# tinyPipes.net
KiCad netlist of a schematic drawn in EAGLE
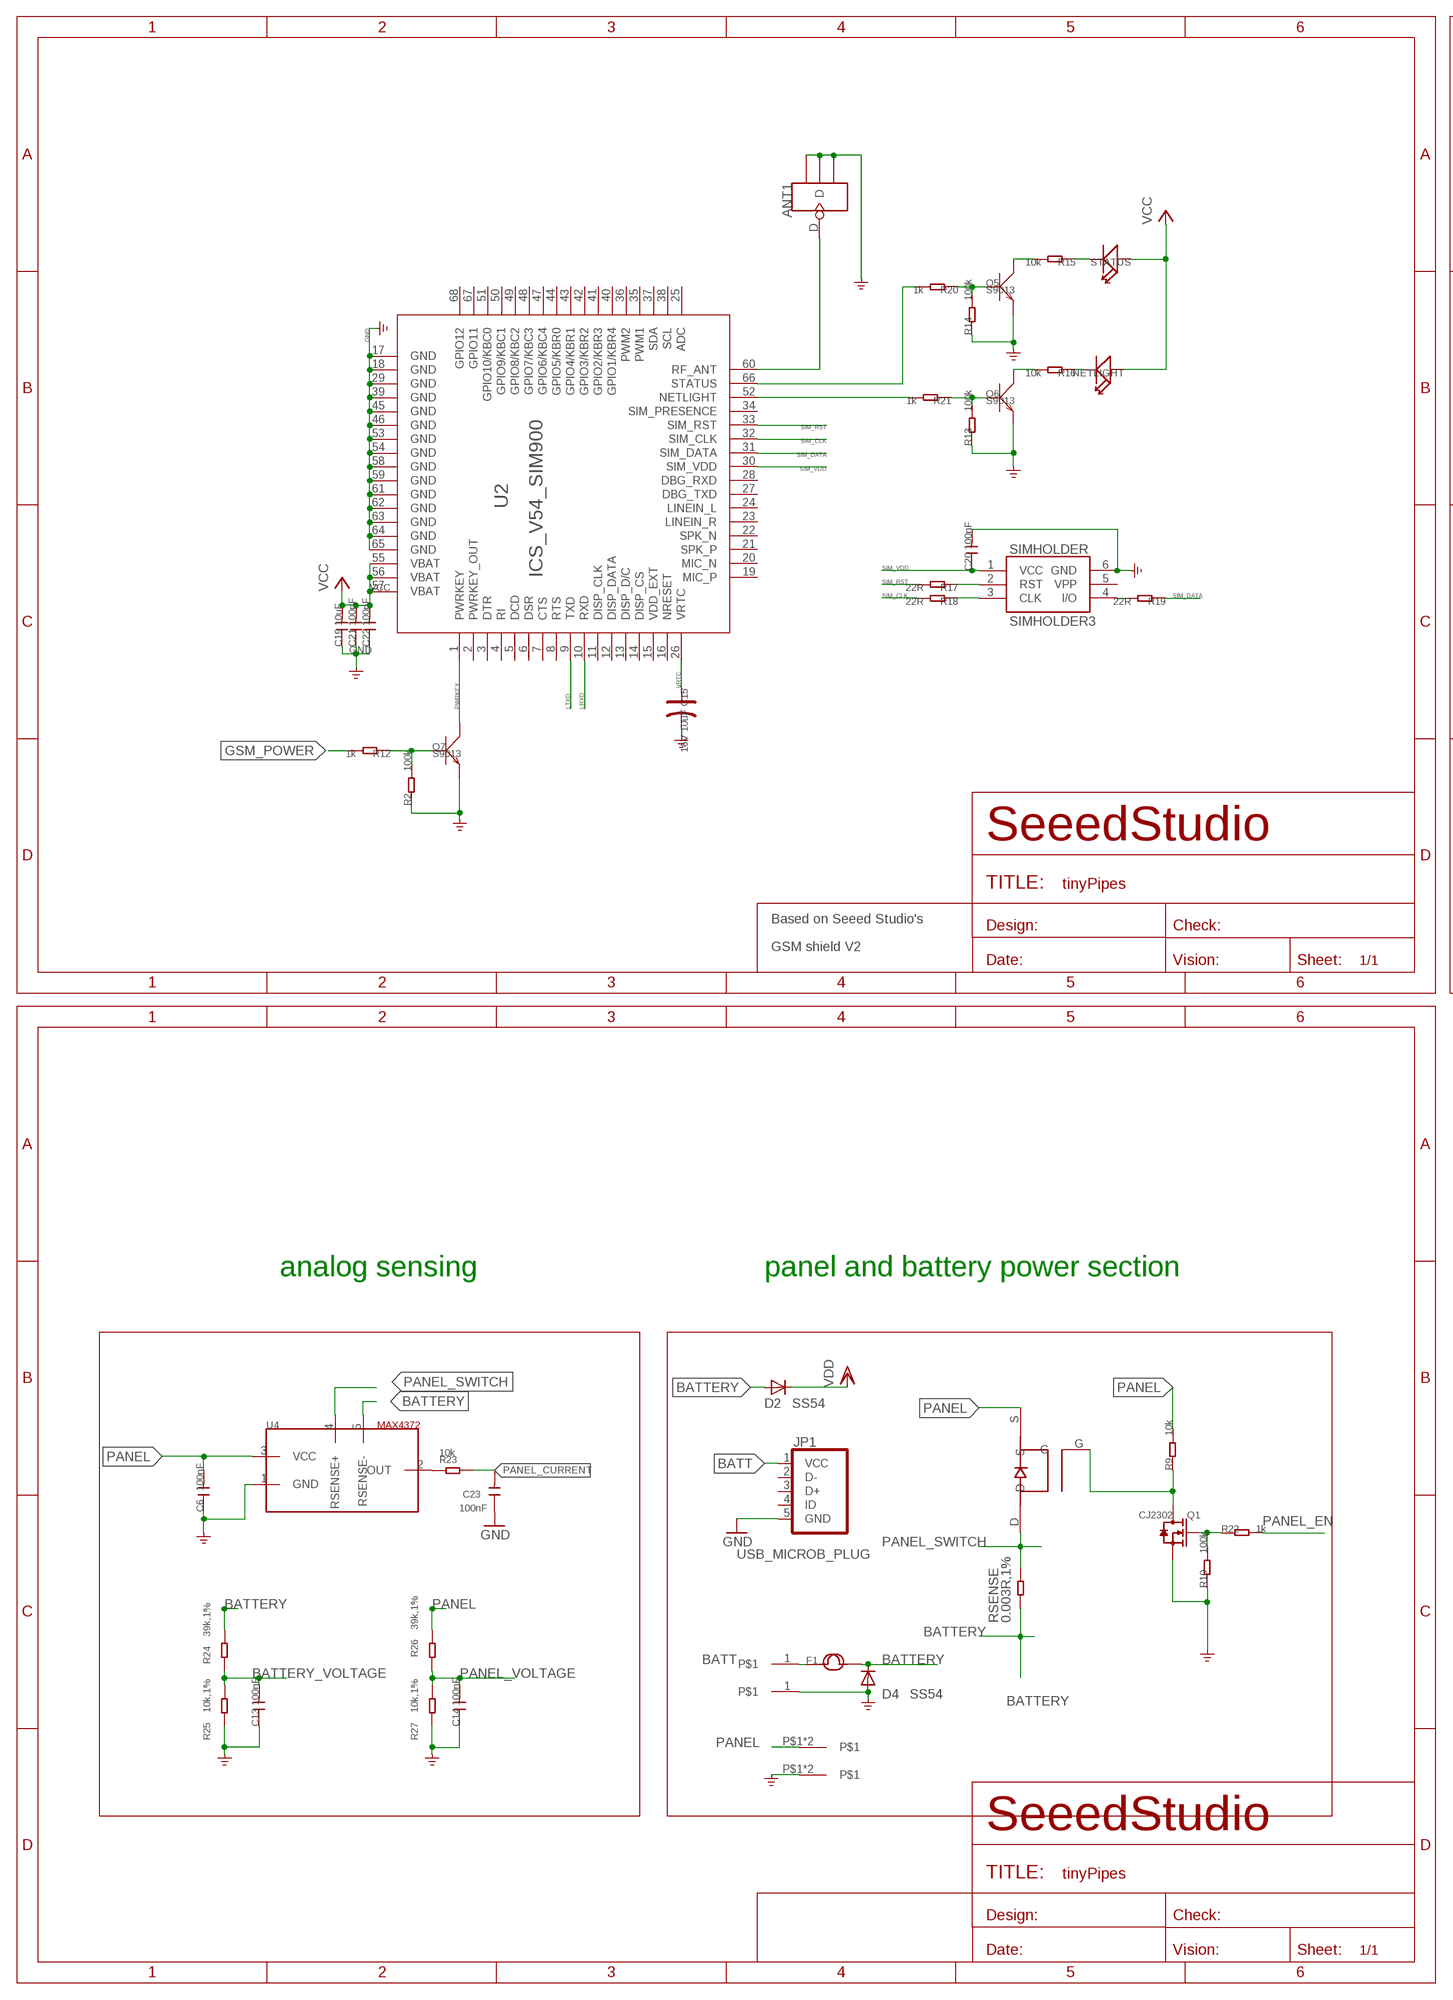
[diagram p0: schematic, sheet 1, part 1 of 2]
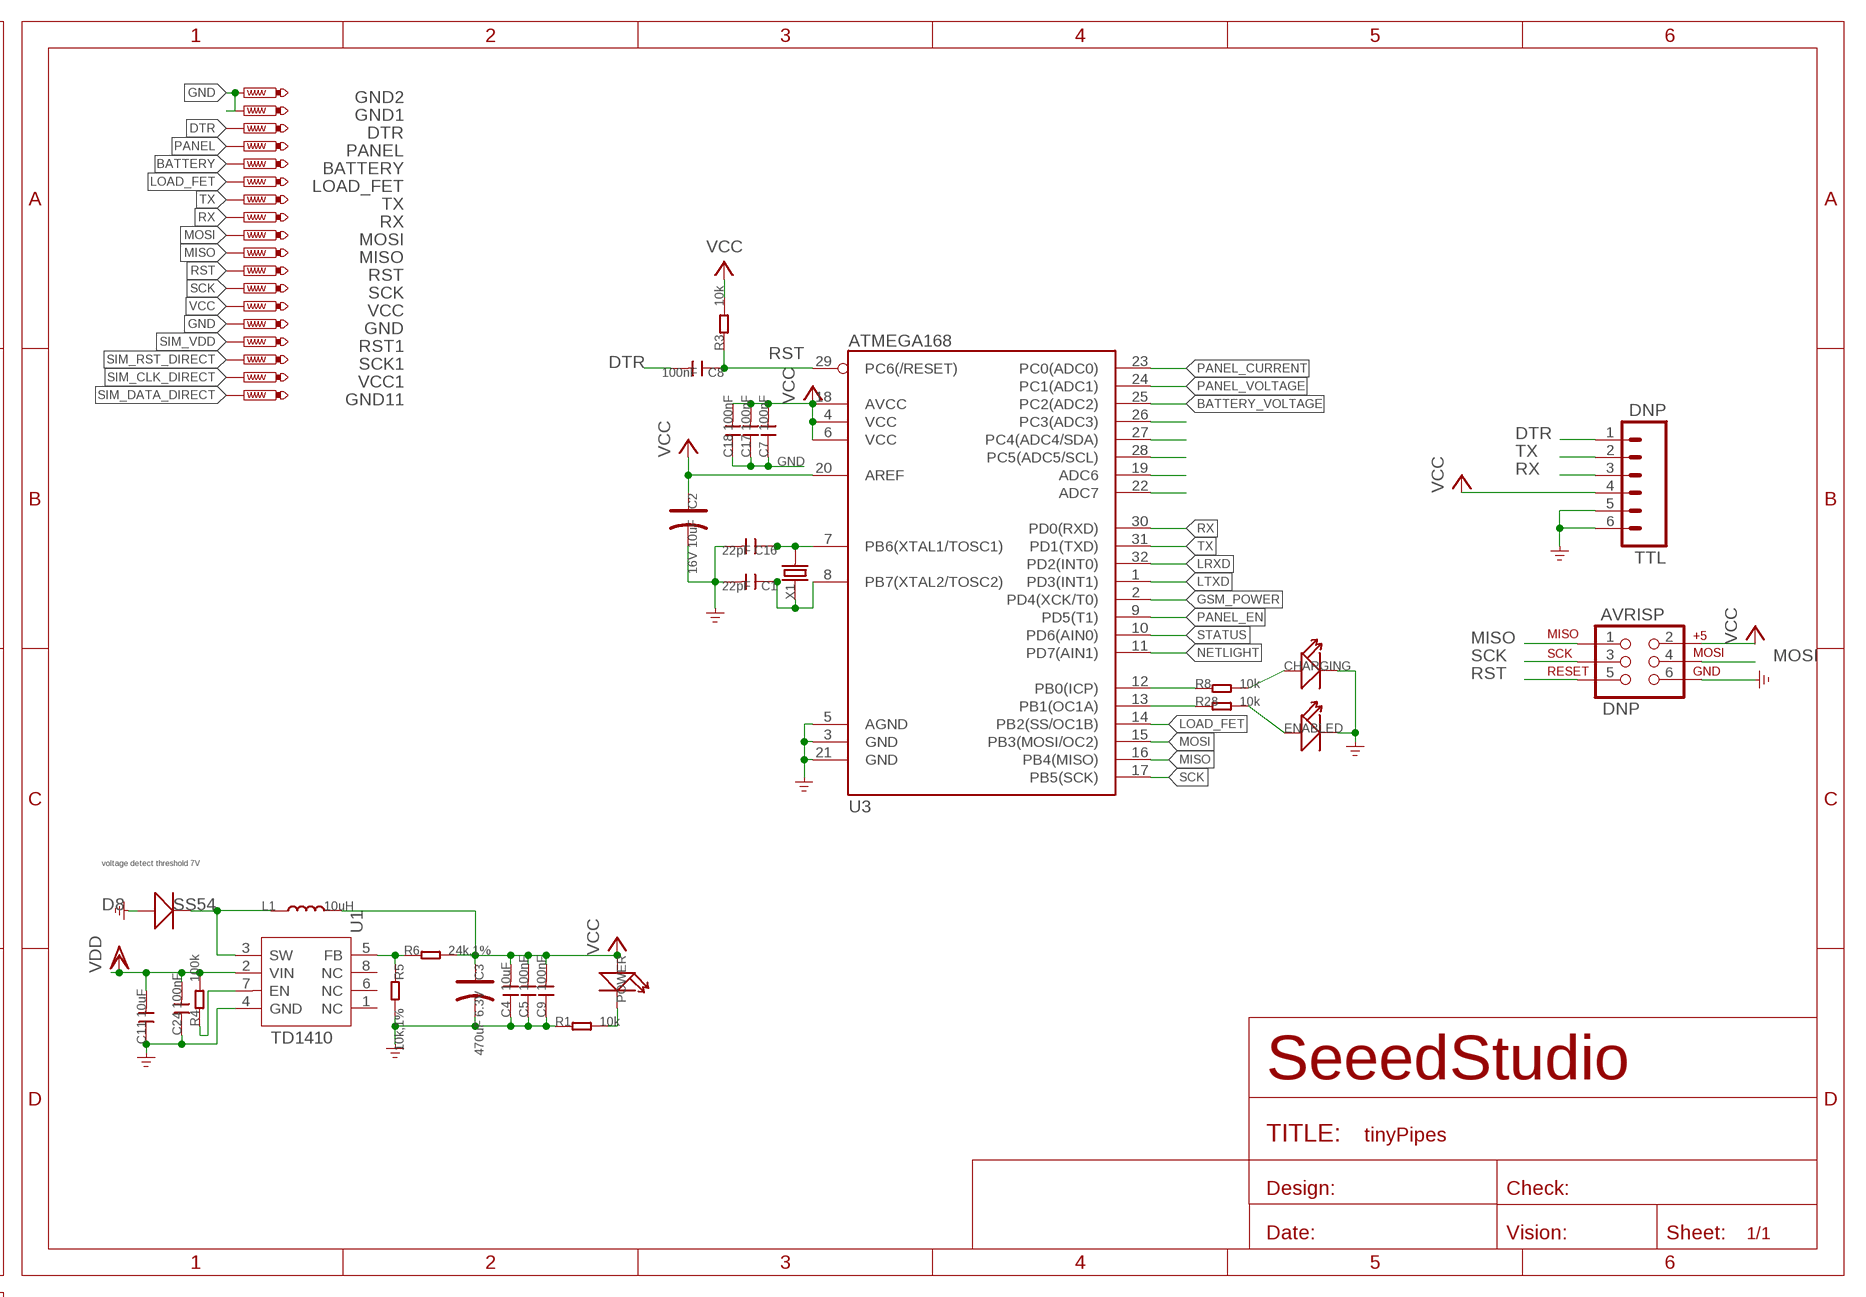
[diagram p1: schematic, sheet 1, part 2 of 2]

(export (version "E")
  (design (tool "Eeschema 10.0.6"))
  (components
    (comp (ref "ANT1")
      (value "ANTENNA-U-FL")
      (footprint "eagle-import:4P-U-FL")
      (libsource (lib "eagle-import") (part "ANTENNA-U-FL"))
    )
    (comp (ref "AVRISP")
      (value "DNP")
      (footprint "eagle-import:2X3_LOCK")
      (libsource (lib "eagle-import") (part "AVR_SPI_PRG_62X3_LOCK"))
    )
    (comp (ref "BATTERY")
      (value "HEARTPAD")
      (footprint "eagle-import:HEART")
      (libsource (lib "eagle-import") (part "HEARTPAD"))
    )
    (comp (ref "BATTERY+")
      (value "TINYPIPES_BATTBATT")
      (footprint "eagle-import:TINYPIPES_BATT")
      (libsource (lib "eagle-import") (part "TINYPIPES_BATTBATT"))
    )
    (comp (ref "BATTERY-")
      (value "TINYPIPES_BATTBATT")
      (footprint "eagle-import:TINYPIPES_BATT")
      (libsource (lib "eagle-import") (part "TINYPIPES_BATTBATT"))
    )
    (comp (ref "C1")
      (value "22pF")
      (footprint "eagle-import:C0603")
      (libsource (lib "eagle-import") (part "C-0603"))
    )
    (comp (ref "C2")
      (value "16V 10uF")
      (footprint "eagle-import:AVX-A")
      (libsource (lib "eagle-import") (part "CAP-AVX-A"))
    )
    (comp (ref "C3")
      (value "470uF 6.3V")
      (footprint "eagle-import:AVX-D")
      (libsource (lib "eagle-import") (part "CAP-AVX-D"))
    )
    (comp (ref "C4")
      (value "10uF")
      (footprint "eagle-import:C0805")
      (libsource (lib "eagle-import") (part "C-0805"))
    )
    (comp (ref "C5")
      (value "100nF")
      (footprint "eagle-import:C0603")
      (libsource (lib "eagle-import") (part "C-0603"))
    )
    (comp (ref "C6")
      (value "100nF")
      (footprint "eagle-import:C0603")
      (libsource (lib "eagle-import") (part "C-0603"))
    )
    (comp (ref "C7")
      (value "100nF")
      (footprint "eagle-import:C0603")
      (libsource (lib "eagle-import") (part "C-0603"))
    )
    (comp (ref "C8")
      (value "100nF")
      (footprint "eagle-import:C0603")
      (libsource (lib "eagle-import") (part "C-0603"))
    )
    (comp (ref "C9")
      (value "100nF")
      (footprint "eagle-import:C0603")
      (libsource (lib "eagle-import") (part "C-0603"))
    )
    (comp (ref "C11")
      (value "10uF")
      (footprint "eagle-import:C0805")
      (libsource (lib "eagle-import") (part "C-0805"))
    )
    (comp (ref "C13")
      (value "100nF")
      (footprint "eagle-import:C0603")
      (libsource (lib "eagle-import") (part "C-0603"))
    )
    (comp (ref "C14")
      (value "100nF")
      (footprint "eagle-import:C0603")
      (libsource (lib "eagle-import") (part "C-0603"))
    )
    (comp (ref "C15")
      (value "16V 10uF")
      (footprint "eagle-import:AVX-A")
      (libsource (lib "eagle-import") (part "CAP-AVX-A"))
    )
    (comp (ref "C16")
      (value "22pF")
      (footprint "eagle-import:C0603")
      (libsource (lib "eagle-import") (part "C-0603"))
    )
    (comp (ref "C17")
      (value "100nF")
      (footprint "eagle-import:C0603")
      (libsource (lib "eagle-import") (part "C-0603"))
    )
    (comp (ref "C18")
      (value "100nF")
      (footprint "eagle-import:C0603")
      (libsource (lib "eagle-import") (part "C-0603"))
    )
    (comp (ref "C19")
      (value "10uF")
      (footprint "eagle-import:C0805")
      (libsource (lib "eagle-import") (part "C-0805"))
    )
    (comp (ref "C20")
      (value "100nF")
      (footprint "eagle-import:C0603")
      (libsource (lib "eagle-import") (part "C-0603"))
    )
    (comp (ref "C21")
      (value "100nF")
      (footprint "eagle-import:C0603")
      (libsource (lib "eagle-import") (part "C-0603"))
    )
    (comp (ref "C22")
      (value "100nF")
      (footprint "eagle-import:C0603")
      (libsource (lib "eagle-import") (part "C-0603"))
    )
    (comp (ref "C23")
      (value "100nF")
      (footprint "eagle-import:C0805")
      (libsource (lib "eagle-import") (part "C-0805"))
    )
    (comp (ref "C24")
      (value "100nF")
      (footprint "eagle-import:C0603")
      (libsource (lib "eagle-import") (part "C-0603"))
    )
    (comp (ref "CHARGING")
      (value "LED'0603'")
      (footprint "eagle-import:LED-0603")
      (libsource (lib "eagle-import") (part "LED'0603'"))
    )
    (comp (ref "D2")
      (value "SS54")
      (footprint "eagle-import:SMB")
      (libsource (lib "eagle-import") (part "DIODE-SMB"))
    )
    (comp (ref "D4")
      (value "SS54")
      (footprint "eagle-import:SMB")
      (libsource (lib "eagle-import") (part "DIODE-SMB"))
    )
    (comp (ref "D8")
      (value "SS54")
      (footprint "eagle-import:SMB")
      (libsource (lib "eagle-import") (part "D'MBRS240LT3'"))
    )
    (comp (ref "DTR")
      (value "HEARTPAD")
      (footprint "eagle-import:HEART")
      (libsource (lib "eagle-import") (part "HEARTPAD"))
    )
    (comp (ref "ENABLED")
      (value "LED'0603'")
      (footprint "eagle-import:LED-0603")
      (libsource (lib "eagle-import") (part "LED'0603'"))
    )
    (comp (ref "F1")
      (value "FUSE'16R700'")
      (footprint "eagle-import:0210")
      (libsource (lib "eagle-import") (part "FUSE'16R700'"))
    )
    (comp (ref "GND")
      (value "HEARTPAD")
      (footprint "eagle-import:HEART")
      (libsource (lib "eagle-import") (part "HEARTPAD"))
    )
    (comp (ref "GND1")
      (value "HEARTPAD")
      (footprint "eagle-import:HEART")
      (libsource (lib "eagle-import") (part "HEARTPAD"))
    )
    (comp (ref "GND2")
      (value "HEARTPAD")
      (footprint "eagle-import:HEART")
      (libsource (lib "eagle-import") (part "HEARTPAD"))
    )
    (comp (ref "GND11")
      (value "HEARTPAD")
      (footprint "eagle-import:HEART")
      (libsource (lib "eagle-import") (part "HEARTPAD"))
    )
    (comp (ref "JP1")
      (value "USB_MICROB_PLUG")
      (footprint "eagle-import:MICRO-B-RA-SMT")
      (libsource (lib "eagle-import") (part "USB_MICROB_PLUG"))
    )
    (comp (ref "L1")
      (value "10uH")
      (footprint "eagle-import:L0630")
      (libsource (lib "eagle-import") (part "L'0630'"))
    )
    (comp (ref "LOAD_FET")
      (value "HEARTPAD")
      (footprint "eagle-import:HEART")
      (libsource (lib "eagle-import") (part "HEARTPAD"))
    )
    (comp (ref "MISO")
      (value "HEARTPAD")
      (footprint "eagle-import:HEART")
      (libsource (lib "eagle-import") (part "HEARTPAD"))
    )
    (comp (ref "MOSI")
      (value "HEARTPAD")
      (footprint "eagle-import:HEART")
      (libsource (lib "eagle-import") (part "HEARTPAD"))
    )
    (comp (ref "NETLIGHT")
      (value "LED'0603'")
      (footprint "eagle-import:LED-0603")
      (libsource (lib "eagle-import") (part "LED'0603'"))
    )
    (comp (ref "PANEL")
      (value "HEARTPAD")
      (footprint "eagle-import:HEART")
      (libsource (lib "eagle-import") (part "HEARTPAD"))
    )
    (comp (ref "PANEL+")
      (value "TINYPIPES_BATTPANEL")
      (footprint "eagle-import:TINYPIPES_PANEL")
      (libsource (lib "eagle-import") (part "TINYPIPES_BATTPANEL"))
    )
    (comp (ref "PANEL-")
      (value "TINYPIPES_BATTPANEL")
      (footprint "eagle-import:TINYPIPES_PANEL")
      (libsource (lib "eagle-import") (part "TINYPIPES_BATTPANEL"))
    )
    (comp (ref "POWER")
      (value "LED'0603'")
      (footprint "eagle-import:LED-0603")
      (libsource (lib "eagle-import") (part "LED'0603'"))
    )
    (comp (ref "Q1")
      (value "CJ2302")
      (footprint "eagle-import:SOT23")
      (libsource (lib "eagle-import") (part "MOSFET-N'SOT23'"))
    )
    (comp (ref "Q5")
      (value "S9013")
      (footprint "eagle-import:SOT23")
      (libsource (lib "eagle-import") (part "TRANSISTOR-NPN-SOT23"))
    )
    (comp (ref "Q6")
      (value "S9013")
      (footprint "eagle-import:SOT23")
      (libsource (lib "eagle-import") (part "TRANSISTOR-NPN-SOT23"))
    )
    (comp (ref "Q7")
      (value "S9013")
      (footprint "eagle-import:SOT23")
      (libsource (lib "eagle-import") (part "TRANSISTOR-NPN-SOT23"))
    )
    (comp (ref "R1")
      (value "10k")
      (footprint "eagle-import:R0603")
      (libsource (lib "eagle-import") (part "R-0603"))
    )
    (comp (ref "R2")
      (value "100k")
      (footprint "eagle-import:R0603")
      (libsource (lib "eagle-import") (part "R-0603"))
    )
    (comp (ref "R3")
      (value "10k")
      (footprint "eagle-import:R0603")
      (libsource (lib "eagle-import") (part "R-0603"))
    )
    (comp (ref "R4")
      (value "100k")
      (footprint "eagle-import:R0603")
      (libsource (lib "eagle-import") (part "R-0603"))
    )
    (comp (ref "R5")
      (value "10k,1%")
      (footprint "eagle-import:R0603")
      (libsource (lib "eagle-import") (part "R-0603"))
    )
    (comp (ref "R6")
      (value "24k,1%")
      (footprint "eagle-import:R0603")
      (libsource (lib "eagle-import") (part "R-0603"))
    )
    (comp (ref "R8")
      (value "10k")
      (footprint "eagle-import:R0603")
      (libsource (lib "eagle-import") (part "R-0603"))
    )
    (comp (ref "R9")
      (value "10k")
      (footprint "eagle-import:R0603")
      (libsource (lib "eagle-import") (part "R-0603"))
    )
    (comp (ref "R10")
      (value "100k")
      (footprint "eagle-import:R0603")
      (libsource (lib "eagle-import") (part "R-0603"))
    )
    (comp (ref "R12")
      (value "1k")
      (footprint "eagle-import:R0603")
      (libsource (lib "eagle-import") (part "R-0603"))
    )
    (comp (ref "R13")
      (value "100k")
      (footprint "eagle-import:R0603")
      (libsource (lib "eagle-import") (part "R-0603"))
    )
    (comp (ref "R14")
      (value "100k")
      (footprint "eagle-import:R0603")
      (libsource (lib "eagle-import") (part "R-0603"))
    )
    (comp (ref "R15")
      (value "10k")
      (footprint "eagle-import:R0603")
      (libsource (lib "eagle-import") (part "R-0603"))
    )
    (comp (ref "R16")
      (value "10k")
      (footprint "eagle-import:R0603")
      (libsource (lib "eagle-import") (part "R-0603"))
    )
    (comp (ref "R17")
      (value "22R")
      (footprint "eagle-import:R0603")
      (libsource (lib "eagle-import") (part "R-0603"))
    )
    (comp (ref "R18")
      (value "22R")
      (footprint "eagle-import:R0603")
      (libsource (lib "eagle-import") (part "R-0603"))
    )
    (comp (ref "R19")
      (value "22R")
      (footprint "eagle-import:R0603")
      (libsource (lib "eagle-import") (part "R-0603"))
    )
    (comp (ref "R20")
      (value "1k")
      (footprint "eagle-import:R0603")
      (libsource (lib "eagle-import") (part "R-0603"))
    )
    (comp (ref "R21")
      (value "1k")
      (footprint "eagle-import:R0603")
      (libsource (lib "eagle-import") (part "R-0603"))
    )
    (comp (ref "R22")
      (value "1k")
      (footprint "eagle-import:R0603")
      (libsource (lib "eagle-import") (part "R-0603"))
    )
    (comp (ref "R23")
      (value "10k")
      (footprint "eagle-import:R0603")
      (libsource (lib "eagle-import") (part "R-0603"))
    )
    (comp (ref "R24")
      (value "39k,1%")
      (footprint "eagle-import:R0603")
      (libsource (lib "eagle-import") (part "R-0603"))
    )
    (comp (ref "R25")
      (value "10k,1%")
      (footprint "eagle-import:R0603")
      (libsource (lib "eagle-import") (part "R-0603"))
    )
    (comp (ref "R26")
      (value "39k,1%")
      (footprint "eagle-import:R0603")
      (libsource (lib "eagle-import") (part "R-0603"))
    )
    (comp (ref "R27")
      (value "10k,1%")
      (footprint "eagle-import:R0603")
      (libsource (lib "eagle-import") (part "R-0603"))
    )
    (comp (ref "R28")
      (value "10k")
      (footprint "eagle-import:R0603")
      (libsource (lib "eagle-import") (part "R-0603"))
    )
    (comp (ref "RSENSE")
      (value "0.003R,1%")
      (footprint "eagle-import:R2512")
      (libsource (lib "eagle-import") (part "R-2512"))
    )
    (comp (ref "RST")
      (value "HEARTPAD")
      (footprint "eagle-import:HEART")
      (libsource (lib "eagle-import") (part "HEARTPAD"))
    )
    (comp (ref "RST1")
      (value "HEARTPAD")
      (footprint "eagle-import:HEART")
      (libsource (lib "eagle-import") (part "HEARTPAD"))
    )
    (comp (ref "RX")
      (value "HEARTPAD")
      (footprint "eagle-import:HEART")
      (libsource (lib "eagle-import") (part "HEARTPAD"))
    )
    (comp (ref "SCK")
      (value "HEARTPAD")
      (footprint "eagle-import:HEART")
      (libsource (lib "eagle-import") (part "HEARTPAD"))
    )
    (comp (ref "SCK1")
      (value "HEARTPAD")
      (footprint "eagle-import:HEART")
      (libsource (lib "eagle-import") (part "HEARTPAD"))
    )
    (comp (ref "SIMHOLDER")
      (value "SIMHOLDER3")
      (footprint "eagle-import:SIMHOLDER3")
      (libsource (lib "eagle-import") (part "SIMHOLDER3"))
    )
    (comp (ref "STATUS")
      (value "LED'0603'")
      (footprint "eagle-import:LED-0603")
      (libsource (lib "eagle-import") (part "LED'0603'"))
    )
    (comp (ref "TTL")
      (value "DNP")
      (footprint "eagle-import:1X06_LOCK")
      (libsource (lib "eagle-import") (part "M06LOCK"))
    )
    (comp (ref "TX")
      (value "HEARTPAD")
      (footprint "eagle-import:HEART")
      (libsource (lib "eagle-import") (part "HEARTPAD"))
    )
    (comp (ref "U1")
      (value "TD1410")
      (footprint "eagle-import:SOP8")
      (libsource (lib "eagle-import") (part "TD1410"))
    )
    (comp (ref "U2")
      (value "ICS_V54_SIM900")
      (footprint "eagle-import:ICS_V54_SIM900")
      (libsource (lib "eagle-import") (part "ICS_V54_SIM900"))
    )
    (comp (ref "U3")
      (value "ATMEGA168")
      (footprint "eagle-import:TQFP32-08")
      (libsource (lib "eagle-import") (part "ATMEGA168"))
    )
    (comp (ref "U4")
      (value "MAX4372")
      (footprint "eagle-import:SOT23-5")
      (libsource (lib "eagle-import") (part "MAX4372"))
    )
    (comp (ref "U5")
      (value "SI4435POWER")
      (footprint "eagle-import:SO8_FET")
      (libsource (lib "eagle-import") (part "SI4435POWER"))
    )
    (comp (ref "VCC")
      (value "HEARTPAD")
      (footprint "eagle-import:HEART")
      (libsource (lib "eagle-import") (part "HEARTPAD"))
    )
    (comp (ref "VCC1")
      (value "HEARTPAD")
      (footprint "eagle-import:HEART")
      (libsource (lib "eagle-import") (part "HEARTPAD"))
    )
    (comp (ref "X1")
      (value "CRYSTAL'5032'")
      (footprint "eagle-import:2P-SMD-5X3.2")
      (libsource (lib "eagle-import") (part "CRYSTAL'5032'"))
    )
  )
  (nets
    (net (code "1") (name "/PWRKEY") (class "Default")
      (node (ref "Q7") (pin "3") (pinfunction "C_3") (pintype "passive"))
      (node (ref "U2") (pin "1") (pinfunction "PWRKEY_1") (pintype "input"))
    )
    (net (code "2") (name "/SIM_CLK") (class "Default")
      (node (ref "R18") (pin "2") (pinfunction "2_2") (pintype "passive"))
      (node (ref "U2") (pin "32") (pinfunction "SIM_CLK_32") (pintype "output"))
    )
    (net (code "3") (name "/SIM_DATA") (class "Default")
      (node (ref "R19") (pin "1") (pinfunction "1_1") (pintype "passive"))
      (node (ref "U2") (pin "31") (pinfunction "SIM_DATA_31") (pintype "bidirectional"))
    )
    (net (code "4") (name "/SIM_RST") (class "Default")
      (node (ref "R17") (pin "2") (pinfunction "2_2") (pintype "passive"))
      (node (ref "U2") (pin "33") (pinfunction "SIM_RST_33") (pintype "output"))
    )
    (net (code "5") (name "/VRTC") (class "Default")
      (node (ref "C15") (pin "+") (pinfunction "+_+") (pintype "passive"))
      (node (ref "U2") (pin "26") (pinfunction "VRTC_26") (pintype "bidirectional"))
    )
    (net (code "6") (name "BATT") (class "Default")
      (node (ref "BATTERY+") (pin "1") (pinfunction "P$1_1") (pintype "bidirectional"))
      (node (ref "F1") (pin "1") (pinfunction "1_1") (pintype "bidirectional"))
      (node (ref "JP1") (pin "1") (pinfunction "VCC_1") (pintype "bidirectional"))
    )
    (net (code "7") (name "BATTERY") (class "Default")
      (node (ref "BATTERY") (pin "P$1") (pinfunction "TP_P$1") (pintype "input"))
      (node (ref "D2") (pin "A") (pinfunction "A_A") (pintype "passive"))
      (node (ref "D4") (pin "C") (pinfunction "C_C") (pintype "passive"))
      (node (ref "F1") (pin "2") (pinfunction "2_2") (pintype "bidirectional"))
      (node (ref "R24") (pin "2") (pinfunction "2_2") (pintype "passive"))
      (node (ref "RSENSE") (pin "1") (pinfunction "1_1") (pintype "passive"))
      (node (ref "U4") (pin "5") (pinfunction "RSENSE-_5") (pintype "bidirectional"))
    )
    (net (code "8") (name "BATTERY_VOLTAGE") (class "Default")
      (node (ref "C13") (pin "2") (pinfunction "2_2") (pintype "passive"))
      (node (ref "R24") (pin "1") (pinfunction "1_1") (pintype "passive"))
      (node (ref "R25") (pin "2") (pinfunction "2_2") (pintype "passive"))
      (node (ref "U3") (pin "25") (pinfunction "PC2(ADC2)_25") (pintype "bidirectional"))
    )
    (net (code "9") (name "DTR") (class "Default")
      (node (ref "C8") (pin "2") (pinfunction "2_2") (pintype "passive"))
      (node (ref "DTR") (pin "P$1") (pinfunction "TP_P$1") (pintype "input"))
      (node (ref "TTL") (pin "1") (pinfunction "1_1") (pintype "passive"))
    )
    (net (code "10") (name "GND") (class "Default")
      (node (ref "ANT1") (pin "GND1") (pinfunction "GND1_GND1") (pintype "bidirectional"))
      (node (ref "ANT1") (pin "GND2") (pinfunction "GND2_GND2") (pintype "bidirectional"))
      (node (ref "ANT1") (pin "GND3") (pinfunction "GND3_GND3") (pintype "bidirectional"))
      (node (ref "AVRISP") (pin "6") (pinfunction "6_6") (pintype "passive"))
      (node (ref "BATTERY-") (pin "1") (pinfunction "P$1_1") (pintype "bidirectional"))
      (node (ref "C1") (pin "2") (pinfunction "2_2") (pintype "passive"))
      (node (ref "C11") (pin "1") (pinfunction "1_1") (pintype "passive"))
      (node (ref "C13") (pin "1") (pinfunction "1_1") (pintype "passive"))
      (node (ref "C14") (pin "1") (pinfunction "1_1") (pintype "passive"))
      (node (ref "C15") (pin "-") (pinfunction "-_-") (pintype "passive"))
      (node (ref "C16") (pin "2") (pinfunction "2_2") (pintype "passive"))
      (node (ref "C17") (pin "1") (pinfunction "1_1") (pintype "passive"))
      (node (ref "C18") (pin "1") (pinfunction "1_1") (pintype "passive"))
      (node (ref "C19") (pin "1") (pinfunction "1_1") (pintype "passive"))
      (node (ref "C2") (pin "-") (pinfunction "-_-") (pintype "passive"))
      (node (ref "C20") (pin "2") (pinfunction "2_2") (pintype "passive"))
      (node (ref "C21") (pin "1") (pinfunction "1_1") (pintype "passive"))
      (node (ref "C22") (pin "1") (pinfunction "1_1") (pintype "passive"))
      (node (ref "C23") (pin "1") (pinfunction "1_1") (pintype "passive"))
      (node (ref "C24") (pin "1") (pinfunction "1_1") (pintype "passive"))
      (node (ref "C3") (pin "-") (pinfunction "-_-") (pintype "passive"))
      (node (ref "C4") (pin "1") (pinfunction "1_1") (pintype "passive"))
      (node (ref "C5") (pin "1") (pinfunction "1_1") (pintype "passive"))
      (node (ref "C6") (pin "1") (pinfunction "1_1") (pintype "passive"))
      (node (ref "C7") (pin "1") (pinfunction "1_1") (pintype "passive"))
      (node (ref "C9") (pin "1") (pinfunction "1_1") (pintype "passive"))
      (node (ref "CHARGING") (pin "-") (pinfunction "-_-") (pintype "passive"))
      (node (ref "D4") (pin "A") (pinfunction "A_A") (pintype "passive"))
      (node (ref "D8") (pin "+") (pinfunction "+_+") (pintype "passive"))
      (node (ref "ENABLED") (pin "-") (pinfunction "-_-") (pintype "passive"))
      (node (ref "GND") (pin "P$1") (pinfunction "TP_P$1") (pintype "input"))
      (node (ref "GND1") (pin "P$1") (pinfunction "TP_P$1") (pintype "input"))
      (node (ref "GND2") (pin "P$1") (pinfunction "TP_P$1") (pintype "input"))
      (node (ref "JP1") (pin "5") (pinfunction "GND_5") (pintype "bidirectional"))
      (node (ref "PANEL-") (pin "P$1") (pinfunction "P$1_P$1") (pintype "bidirectional"))
      (node (ref "PANEL-") (pin "P$2") (pinfunction "P$1_P$2") (pintype "bidirectional"))
      (node (ref "Q1") (pin "2") (pinfunction "S_2") (pintype "passive"))
      (node (ref "Q5") (pin "2") (pinfunction "E_2") (pintype "passive"))
      (node (ref "Q6") (pin "2") (pinfunction "E_2") (pintype "passive"))
      (node (ref "Q7") (pin "2") (pinfunction "E_2") (pintype "passive"))
      (node (ref "R1") (pin "1") (pinfunction "1_1") (pintype "passive"))
      (node (ref "R10") (pin "1") (pinfunction "1_1") (pintype "passive"))
      (node (ref "R13") (pin "1") (pinfunction "1_1") (pintype "passive"))
      (node (ref "R14") (pin "1") (pinfunction "1_1") (pintype "passive"))
      (node (ref "R2") (pin "1") (pinfunction "1_1") (pintype "passive"))
      (node (ref "R25") (pin "1") (pinfunction "1_1") (pintype "passive"))
      (node (ref "R27") (pin "1") (pinfunction "1_1") (pintype "passive"))
      (node (ref "R5") (pin "2") (pinfunction "2_2") (pintype "passive"))
      (node (ref "SIMHOLDER") (pin "6") (pinfunction "GND_6") (pintype "bidirectional"))
      (node (ref "TTL") (pin "5") (pinfunction "5_5") (pintype "passive"))
      (node (ref "TTL") (pin "6") (pinfunction "6_6") (pintype "passive"))
      (node (ref "U1") (pin "4") (pinfunction "GND_4") (pintype "power_in"))
      (node (ref "U2") (pin "17") (pinfunction "GND_17") (pintype "power_in"))
      (node (ref "U2") (pin "18") (pinfunction "GND_18") (pintype "power_in"))
      (node (ref "U2") (pin "29") (pinfunction "GND_29") (pintype "power_in"))
      (node (ref "U2") (pin "39") (pinfunction "GND_39") (pintype "power_in"))
      (node (ref "U2") (pin "45") (pinfunction "GND_45") (pintype "power_in"))
      (node (ref "U2") (pin "46") (pinfunction "GND_46") (pintype "power_in"))
      (node (ref "U2") (pin "53") (pinfunction "GND_53") (pintype "power_in"))
      (node (ref "U2") (pin "54") (pinfunction "GND_54") (pintype "power_in"))
      (node (ref "U2") (pin "58") (pinfunction "GND_58") (pintype "power_in"))
      (node (ref "U2") (pin "59") (pinfunction "GND_59") (pintype "power_in"))
      (node (ref "U2") (pin "61") (pinfunction "GND_61") (pintype "power_in"))
      (node (ref "U2") (pin "62") (pinfunction "GND_62") (pintype "power_in"))
      (node (ref "U2") (pin "63") (pinfunction "GND_63") (pintype "power_in"))
      (node (ref "U2") (pin "64") (pinfunction "GND_64") (pintype "power_in"))
      (node (ref "U2") (pin "65") (pinfunction "GND_65") (pintype "power_in"))
      (node (ref "U3") (pin "21") (pinfunction "GND_21") (pintype "bidirectional"))
      (node (ref "U3") (pin "3") (pinfunction "GND_3") (pintype "bidirectional"))
      (node (ref "U3") (pin "5") (pinfunction "AGND_5") (pintype "bidirectional"))
      (node (ref "U4") (pin "1") (pinfunction "GND_1") (pintype "bidirectional"))
    )
    (net (code "11") (name "GSM_POWER") (class "Default")
      (node (ref "R12") (pin "2") (pinfunction "2_2") (pintype "passive"))
      (node (ref "U3") (pin "2") (pinfunction "PD4(XCK/T0)_2") (pintype "bidirectional"))
    )
    (net (code "12") (name "LOAD_FET") (class "Default")
      (node (ref "LOAD_FET") (pin "P$1") (pinfunction "TP_P$1") (pintype "input"))
      (node (ref "U3") (pin "14") (pinfunction "PB2(SS/OC1B)_14") (pintype "bidirectional"))
    )
    (net (code "13") (name "LRXD") (class "Default")
      (node (ref "U2") (pin "10") (pinfunction "RXD_10") (pintype "input"))
      (node (ref "U3") (pin "32") (pinfunction "PD2(INT0)_32") (pintype "bidirectional"))
    )
    (net (code "14") (name "LTXD") (class "Default")
      (node (ref "U2") (pin "9") (pinfunction "TXD_9") (pintype "output"))
      (node (ref "U3") (pin "1") (pinfunction "PD3(INT1)_1") (pintype "bidirectional"))
    )
    (net (code "15") (name "MISO") (class "Default")
      (node (ref "AVRISP") (pin "1") (pinfunction "1_1") (pintype "passive"))
      (node (ref "MISO") (pin "P$1") (pinfunction "TP_P$1") (pintype "input"))
      (node (ref "U3") (pin "16") (pinfunction "PB4(MISO)_16") (pintype "bidirectional"))
    )
    (net (code "16") (name "MOSI") (class "Default")
      (node (ref "AVRISP") (pin "4") (pinfunction "4_4") (pintype "passive"))
      (node (ref "MOSI") (pin "P$1") (pinfunction "TP_P$1") (pintype "input"))
      (node (ref "U3") (pin "15") (pinfunction "PB3(MOSI/OC2)_15") (pintype "bidirectional"))
    )
    (net (code "17") (name "NETLIGHT") (class "Default")
      (node (ref "R21") (pin "2") (pinfunction "2_2") (pintype "passive"))
      (node (ref "U2") (pin "52") (pinfunction "NETLIGHT_52") (pintype "output"))
      (node (ref "U3") (pin "11") (pinfunction "PD7(AIN1)_11") (pintype "bidirectional"))
    )
    (net (code "18") (name "Net-(CHARGING-Pad+)") (class "Default")
      (node (ref "CHARGING") (pin "+") (pinfunction "+_+") (pintype "passive"))
      (node (ref "R8") (pin "2") (pinfunction "2_2") (pintype "passive"))
    )
    (net (code "19") (name "Net-(ENABLED-Pad+)") (class "Default")
      (node (ref "ENABLED") (pin "+") (pinfunction "+_+") (pintype "passive"))
      (node (ref "R28") (pin "2") (pinfunction "2_2") (pintype "passive"))
    )
    (net (code "20") (name "Net-(NETLIGHT-Pad-)") (class "Default")
      (node (ref "NETLIGHT") (pin "-") (pinfunction "-_-") (pintype "passive"))
      (node (ref "R16") (pin "1") (pinfunction "1_1") (pintype "passive"))
    )
    (net (code "21") (name "Net-(POWER-Pad-)") (class "Default")
      (node (ref "POWER") (pin "-") (pinfunction "-_-") (pintype "passive"))
      (node (ref "R1") (pin "2") (pinfunction "2_2") (pintype "passive"))
    )
    (net (code "22") (name "Net-(Q1-D)") (class "Default")
      (node (ref "Q1") (pin "3") (pinfunction "D_3") (pintype "passive"))
      (node (ref "R9") (pin "1") (pinfunction "1_1") (pintype "passive"))
      (node (ref "U5") (pin "G") (pinfunction "G_G") (pintype "bidirectional"))
    )
    (net (code "23") (name "Net-(Q1-G)") (class "Default")
      (node (ref "Q1") (pin "1") (pinfunction "G_1") (pintype "passive"))
      (node (ref "R10") (pin "2") (pinfunction "2_2") (pintype "passive"))
      (node (ref "R22") (pin "1") (pinfunction "1_1") (pintype "passive"))
    )
    (net (code "24") (name "Net-(Q5-B)") (class "Default")
      (node (ref "Q5") (pin "1") (pinfunction "B_1") (pintype "passive"))
      (node (ref "R14") (pin "2") (pinfunction "2_2") (pintype "passive"))
      (node (ref "R20") (pin "1") (pinfunction "1_1") (pintype "passive"))
    )
    (net (code "25") (name "Net-(Q5-C)") (class "Default")
      (node (ref "Q5") (pin "3") (pinfunction "C_3") (pintype "passive"))
      (node (ref "R15") (pin "2") (pinfunction "2_2") (pintype "passive"))
    )
    (net (code "26") (name "Net-(Q6-B)") (class "Default")
      (node (ref "Q6") (pin "1") (pinfunction "B_1") (pintype "passive"))
      (node (ref "R13") (pin "2") (pinfunction "2_2") (pintype "passive"))
      (node (ref "R21") (pin "1") (pinfunction "1_1") (pintype "passive"))
    )
    (net (code "27") (name "Net-(Q6-C)") (class "Default")
      (node (ref "Q6") (pin "3") (pinfunction "C_3") (pintype "passive"))
      (node (ref "R16") (pin "2") (pinfunction "2_2") (pintype "passive"))
    )
    (net (code "28") (name "Net-(Q7-B)") (class "Default")
      (node (ref "Q7") (pin "1") (pinfunction "B_1") (pintype "passive"))
      (node (ref "R12") (pin "1") (pinfunction "1_1") (pintype "passive"))
      (node (ref "R2") (pin "2") (pinfunction "2_2") (pintype "passive"))
    )
    (net (code "29") (name "Net-(R15-Pad1)") (class "Default")
      (node (ref "R15") (pin "1") (pinfunction "1_1") (pintype "passive"))
      (node (ref "STATUS") (pin "-") (pinfunction "-_-") (pintype "passive"))
    )
    (net (code "30") (name "Net-(U1-EN)") (class "Default")
      (node (ref "R4") (pin "1") (pinfunction "1_1") (pintype "passive"))
      (node (ref "U1") (pin "7") (pinfunction "EN_7") (pintype "input"))
    )
    (net (code "31") (name "Net-(U1-FB)") (class "Default")
      (node (ref "R5") (pin "1") (pinfunction "1_1") (pintype "passive"))
      (node (ref "R6") (pin "1") (pinfunction "1_1") (pintype "passive"))
      (node (ref "U1") (pin "5") (pinfunction "FB_5") (pintype "input"))
    )
    (net (code "32") (name "Net-(U1-SW)") (class "Default")
      (node (ref "D8") (pin "-") (pinfunction "-_-") (pintype "passive"))
      (node (ref "L1") (pin "1") (pinfunction "1_1") (pintype "passive"))
      (node (ref "U1") (pin "3") (pinfunction "SW_3") (pintype "output"))
    )
    (net (code "33") (name "Net-(U2-RF_ANT)") (class "Default")
      (node (ref "ANT1") (pin "D") (pinfunction "D_D") (pintype "bidirectional"))
      (node (ref "U2") (pin "60") (pinfunction "RF_ANT_60") (pintype "bidirectional"))
    )
    (net (code "34") (name "Net-(U3-PB0(ICP))") (class "Default")
      (node (ref "R8") (pin "1") (pinfunction "1_1") (pintype "passive"))
      (node (ref "U3") (pin "12") (pinfunction "PB0(ICP)_12") (pintype "bidirectional"))
    )
    (net (code "35") (name "Net-(U3-PB1(OC1A))") (class "Default")
      (node (ref "R28") (pin "1") (pinfunction "1_1") (pintype "passive"))
      (node (ref "U3") (pin "13") (pinfunction "PB1(OC1A)_13") (pintype "bidirectional"))
    )
    (net (code "36") (name "Net-(U3-PB6(XTAL1{slash}TOSC1))") (class "Default")
      (node (ref "C16") (pin "1") (pinfunction "1_1") (pintype "passive"))
      (node (ref "U3") (pin "7") (pinfunction "PB6(XTAL1/TOSC1)_7") (pintype "bidirectional"))
      (node (ref "X1") (pin "2") (pinfunction "2_2") (pintype "passive"))
    )
    (net (code "37") (name "Net-(U3-PB7(XTAL2{slash}TOSC2))") (class "Default")
      (node (ref "C1") (pin "1") (pinfunction "1_1") (pintype "passive"))
      (node (ref "U3") (pin "8") (pinfunction "PB7(XTAL2/TOSC2)_8") (pintype "bidirectional"))
      (node (ref "X1") (pin "1") (pinfunction "1_1") (pintype "passive"))
    )
    (net (code "38") (name "Net-(U4-OUT)") (class "Default")
      (node (ref "R23") (pin "1") (pinfunction "1_1") (pintype "passive"))
      (node (ref "U4") (pin "2") (pinfunction "OUT_2") (pintype "bidirectional"))
    )
    (net (code "39") (name "PANEL") (class "Default")
      (node (ref "C6") (pin "2") (pinfunction "2_2") (pintype "passive"))
      (node (ref "PANEL") (pin "P$1") (pinfunction "TP_P$1") (pintype "input"))
      (node (ref "PANEL+") (pin "P$1") (pinfunction "P$1_P$1") (pintype "bidirectional"))
      (node (ref "PANEL+") (pin "P$2") (pinfunction "P$1_P$2") (pintype "bidirectional"))
      (node (ref "R26") (pin "2") (pinfunction "2_2") (pintype "passive"))
      (node (ref "R9") (pin "2") (pinfunction "2_2") (pintype "passive"))
      (node (ref "U4") (pin "3") (pinfunction "VCC_3") (pintype "bidirectional"))
      (node (ref "U5") (pin "S") (pinfunction "S_S") (pintype "bidirectional"))
    )
    (net (code "40") (name "PANEL_CURRENT") (class "Default")
      (node (ref "C23") (pin "2") (pinfunction "2_2") (pintype "passive"))
      (node (ref "R23") (pin "2") (pinfunction "2_2") (pintype "passive"))
      (node (ref "U3") (pin "23") (pinfunction "PC0(ADC0)_23") (pintype "bidirectional"))
    )
    (net (code "41") (name "PANEL_EN") (class "Default")
      (node (ref "R22") (pin "2") (pinfunction "2_2") (pintype "passive"))
      (node (ref "U3") (pin "9") (pinfunction "PD5(T1)_9") (pintype "bidirectional"))
    )
    (net (code "42") (name "PANEL_SWITCH") (class "Default")
      (node (ref "RSENSE") (pin "2") (pinfunction "2_2") (pintype "passive"))
      (node (ref "U4") (pin "4") (pinfunction "RSENSE+_4") (pintype "bidirectional"))
      (node (ref "U5") (pin "D") (pinfunction "D_D") (pintype "bidirectional"))
    )
    (net (code "43") (name "PANEL_VOLTAGE") (class "Default")
      (node (ref "C14") (pin "2") (pinfunction "2_2") (pintype "passive"))
      (node (ref "R26") (pin "1") (pinfunction "1_1") (pintype "passive"))
      (node (ref "R27") (pin "2") (pinfunction "2_2") (pintype "passive"))
      (node (ref "U3") (pin "24") (pinfunction "PC1(ADC1)_24") (pintype "bidirectional"))
    )
    (net (code "44") (name "RST") (class "Default")
      (node (ref "AVRISP") (pin "5") (pinfunction "5_5") (pintype "passive"))
      (node (ref "C8") (pin "1") (pinfunction "1_1") (pintype "passive"))
      (node (ref "R3") (pin "1") (pinfunction "1_1") (pintype "passive"))
      (node (ref "RST") (pin "P$1") (pinfunction "TP_P$1") (pintype "input"))
      (node (ref "U3") (pin "29") (pinfunction "PC6(/RESET)_29") (pintype "bidirectional"))
    )
    (net (code "45") (name "RX") (class "Default")
      (node (ref "RX") (pin "P$1") (pinfunction "TP_P$1") (pintype "input"))
      (node (ref "TTL") (pin "3") (pinfunction "3_3") (pintype "passive"))
      (node (ref "U3") (pin "30") (pinfunction "PD0(RXD)_30") (pintype "bidirectional"))
    )
    (net (code "46") (name "SCK") (class "Default")
      (node (ref "AVRISP") (pin "3") (pinfunction "3_3") (pintype "passive"))
      (node (ref "SCK") (pin "P$1") (pinfunction "TP_P$1") (pintype "input"))
      (node (ref "U3") (pin "17") (pinfunction "PB5(SCK)_17") (pintype "bidirectional"))
    )
    (net (code "47") (name "SIM_CLK_DIRECT") (class "Default")
      (node (ref "R18") (pin "1") (pinfunction "1_1") (pintype "passive"))
      (node (ref "SIMHOLDER") (pin "3") (pinfunction "CLK_3") (pintype "bidirectional"))
      (node (ref "VCC1") (pin "P$1") (pinfunction "TP_P$1") (pintype "input"))
    )
    (net (code "48") (name "SIM_DATA_DIRECT") (class "Default")
      (node (ref "GND11") (pin "P$1") (pinfunction "TP_P$1") (pintype "input"))
      (node (ref "R19") (pin "2") (pinfunction "2_2") (pintype "passive"))
      (node (ref "SIMHOLDER") (pin "4") (pinfunction "I/O_4") (pintype "bidirectional"))
    )
    (net (code "49") (name "SIM_RST_DIRECT") (class "Default")
      (node (ref "R17") (pin "1") (pinfunction "1_1") (pintype "passive"))
      (node (ref "SCK1") (pin "P$1") (pinfunction "TP_P$1") (pintype "input"))
      (node (ref "SIMHOLDER") (pin "2") (pinfunction "RST_2") (pintype "bidirectional"))
    )
    (net (code "50") (name "SIM_VDD") (class "Default")
      (node (ref "C20") (pin "1") (pinfunction "1_1") (pintype "passive"))
      (node (ref "RST1") (pin "P$1") (pinfunction "TP_P$1") (pintype "input"))
      (node (ref "SIMHOLDER") (pin "1") (pinfunction "VCC_1") (pintype "bidirectional"))
      (node (ref "U2") (pin "30") (pinfunction "SIM_VDD_30") (pintype "output"))
    )
    (net (code "51") (name "STATUS") (class "Default")
      (node (ref "R20") (pin "2") (pinfunction "2_2") (pintype "passive"))
      (node (ref "U2") (pin "66") (pinfunction "STATUS_66") (pintype "output"))
      (node (ref "U3") (pin "10") (pinfunction "PD6(AIN0)_10") (pintype "bidirectional"))
    )
    (net (code "52") (name "TX") (class "Default")
      (node (ref "TTL") (pin "2") (pinfunction "2_2") (pintype "passive"))
      (node (ref "TX") (pin "P$1") (pinfunction "TP_P$1") (pintype "input"))
      (node (ref "U3") (pin "31") (pinfunction "PD1(TXD)_31") (pintype "bidirectional"))
    )
    (net (code "53") (name "VCC") (class "Default")
      (node (ref "AVRISP") (pin "2") (pinfunction "2_2") (pintype "passive"))
      (node (ref "C17") (pin "2") (pinfunction "2_2") (pintype "passive"))
      (node (ref "C18") (pin "2") (pinfunction "2_2") (pintype "passive"))
      (node (ref "C19") (pin "2") (pinfunction "2_2") (pintype "passive"))
      (node (ref "C2") (pin "+") (pinfunction "+_+") (pintype "passive"))
      (node (ref "C21") (pin "2") (pinfunction "2_2") (pintype "passive"))
      (node (ref "C22") (pin "2") (pinfunction "2_2") (pintype "passive"))
      (node (ref "C3") (pin "+") (pinfunction "+_+") (pintype "passive"))
      (node (ref "C4") (pin "2") (pinfunction "2_2") (pintype "passive"))
      (node (ref "C5") (pin "2") (pinfunction "2_2") (pintype "passive"))
      (node (ref "C7") (pin "2") (pinfunction "2_2") (pintype "passive"))
      (node (ref "C9") (pin "2") (pinfunction "2_2") (pintype "passive"))
      (node (ref "L1") (pin "2") (pinfunction "2_2") (pintype "passive"))
      (node (ref "NETLIGHT") (pin "+") (pinfunction "+_+") (pintype "passive"))
      (node (ref "POWER") (pin "+") (pinfunction "+_+") (pintype "passive"))
      (node (ref "R3") (pin "2") (pinfunction "2_2") (pintype "passive"))
      (node (ref "R6") (pin "2") (pinfunction "2_2") (pintype "passive"))
      (node (ref "STATUS") (pin "+") (pinfunction "+_+") (pintype "passive"))
      (node (ref "TTL") (pin "4") (pinfunction "4_4") (pintype "passive"))
      (node (ref "U2") (pin "55") (pinfunction "VBAT_55") (pintype "power_in"))
      (node (ref "U2") (pin "56") (pinfunction "VBAT_56") (pintype "power_in"))
      (node (ref "U2") (pin "57") (pinfunction "VBAT_57") (pintype "power_in"))
      (node (ref "U3") (pin "18") (pinfunction "AVCC_18") (pintype "bidirectional"))
      (node (ref "U3") (pin "20") (pinfunction "AREF_20") (pintype "bidirectional"))
      (node (ref "U3") (pin "4") (pinfunction "VCC_4") (pintype "bidirectional"))
      (node (ref "U3") (pin "6") (pinfunction "VCC_6") (pintype "bidirectional"))
      (node (ref "VCC") (pin "P$1") (pinfunction "TP_P$1") (pintype "input"))
    )
    (net (code "54") (name "VDD") (class "Default")
      (node (ref "C11") (pin "2") (pinfunction "2_2") (pintype "passive"))
      (node (ref "C24") (pin "2") (pinfunction "2_2") (pintype "passive"))
      (node (ref "D2") (pin "C") (pinfunction "C_C") (pintype "passive"))
      (node (ref "R4") (pin "2") (pinfunction "2_2") (pintype "passive"))
      (node (ref "U1") (pin "2") (pinfunction "VIN_2") (pintype "input"))
    )
    (net (code "55") (name "unconnected-(JP1-D+-Pad3)") (class "Default")
      (node (ref "JP1") (pin "3") (pinfunction "D+_3") (pintype "bidirectional"))
    )
    (net (code "56") (name "unconnected-(JP1-D--Pad2)") (class "Default")
      (node (ref "JP1") (pin "2") (pinfunction "D-_2") (pintype "bidirectional"))
    )
    (net (code "57") (name "unconnected-(JP1-ID-Pad4)") (class "Default")
      (node (ref "JP1") (pin "4") (pinfunction "ID_4") (pintype "bidirectional"))
    )
    (net (code "58") (name "unconnected-(SIMHOLDER-VPP-Pad5)") (class "Default")
      (node (ref "SIMHOLDER") (pin "5") (pinfunction "VPP_5") (pintype "bidirectional"))
    )
    (net (code "59") (name "unconnected-(U1-NC-Pad1)") (class "Default")
      (node (ref "U1") (pin "1") (pinfunction "NC_1") (pintype "no_connect"))
    )
    (net (code "60") (name "unconnected-(U1-NC-Pad6)") (class "Default")
      (node (ref "U1") (pin "6") (pinfunction "NC_6") (pintype "no_connect"))
    )
    (net (code "61") (name "unconnected-(U1-NC-Pad8)") (class "Default")
      (node (ref "U1") (pin "8") (pinfunction "NC_8") (pintype "no_connect"))
    )
    (net (code "62") (name "unconnected-(U2-ADC-Pad25)") (class "Default")
      (node (ref "U2") (pin "25") (pinfunction "ADC_25") (pintype "input"))
    )
    (net (code "63") (name "unconnected-(U2-CTS-Pad7)") (class "Default")
      (node (ref "U2") (pin "7") (pinfunction "CTS_7") (pintype "output"))
    )
    (net (code "64") (name "unconnected-(U2-DBG_RXD-Pad28)") (class "Default")
      (node (ref "U2") (pin "28") (pinfunction "DBG_RXD_28") (pintype "input"))
    )
    (net (code "65") (name "unconnected-(U2-DBG_TXD-Pad27)") (class "Default")
      (node (ref "U2") (pin "27") (pinfunction "DBG_TXD_27") (pintype "output"))
    )
    (net (code "66") (name "unconnected-(U2-DCD-Pad5)") (class "Default")
      (node (ref "U2") (pin "5") (pinfunction "DCD_5") (pintype "output"))
    )
    (net (code "67") (name "unconnected-(U2-DISP_CLK-Pad11)") (class "Default")
      (node (ref "U2") (pin "11") (pinfunction "DISP_CLK_11") (pintype "output"))
    )
    (net (code "68") (name "unconnected-(U2-DISP_CS-Pad14)") (class "Default")
      (node (ref "U2") (pin "14") (pinfunction "DISP_CS_14") (pintype "output"))
    )
    (net (code "69") (name "unconnected-(U2-DISP_DATA-Pad12)") (class "Default")
      (node (ref "U2") (pin "12") (pinfunction "DISP_DATA_12") (pintype "bidirectional"))
    )
    (net (code "70") (name "unconnected-(U2-DISP_D{slash}C-Pad13)") (class "Default")
      (node (ref "U2") (pin "13") (pinfunction "DISP_D/C_13") (pintype "output"))
    )
    (net (code "71") (name "unconnected-(U2-DSR-Pad6)") (class "Default")
      (node (ref "U2") (pin "6") (pinfunction "DSR_6") (pintype "output"))
    )
    (net (code "72") (name "unconnected-(U2-DTR-Pad3)") (class "Default")
      (node (ref "U2") (pin "3") (pinfunction "DTR_3") (pintype "input"))
    )
    (net (code "73") (name "unconnected-(U2-GPIO1{slash}KBR4-Pad40)") (class "Default")
      (node (ref "U2") (pin "40") (pinfunction "GPIO1/KBR4_40") (pintype "output"))
    )
    (net (code "74") (name "unconnected-(U2-GPIO2{slash}KBR3-Pad41)") (class "Default")
      (node (ref "U2") (pin "41") (pinfunction "GPIO2/KBR3_41") (pintype "output"))
    )
    (net (code "75") (name "unconnected-(U2-GPIO3{slash}KBR2-Pad42)") (class "Default")
      (node (ref "U2") (pin "42") (pinfunction "GPIO3/KBR2_42") (pintype "output"))
    )
    (net (code "76") (name "unconnected-(U2-GPIO4{slash}KBR1-Pad43)") (class "Default")
      (node (ref "U2") (pin "43") (pinfunction "GPIO4/KBR1_43") (pintype "output"))
    )
    (net (code "77") (name "unconnected-(U2-GPIO5{slash}KBR0-Pad44)") (class "Default")
      (node (ref "U2") (pin "44") (pinfunction "GPIO5/KBR0_44") (pintype "output"))
    )
    (net (code "78") (name "unconnected-(U2-GPIO6{slash}KBC4-Pad47)") (class "Default")
      (node (ref "U2") (pin "47") (pinfunction "GPIO6/KBC4_47") (pintype "input"))
    )
    (net (code "79") (name "unconnected-(U2-GPIO7{slash}KBC3-Pad48)") (class "Default")
      (node (ref "U2") (pin "48") (pinfunction "GPIO7/KBC3_48") (pintype "bidirectional"))
    )
    (net (code "80") (name "unconnected-(U2-GPIO8{slash}KBC2-Pad49)") (class "Default")
      (node (ref "U2") (pin "49") (pinfunction "GPIO8/KBC2_49") (pintype "input"))
    )
    (net (code "81") (name "unconnected-(U2-GPIO9{slash}KBC1-Pad50)") (class "Default")
      (node (ref "U2") (pin "50") (pinfunction "GPIO9/KBC1_50") (pintype "input"))
    )
    (net (code "82") (name "unconnected-(U2-GPIO10{slash}KBC0-Pad51)") (class "Default")
      (node (ref "U2") (pin "51") (pinfunction "GPIO10/KBC0_51") (pintype "bidirectional"))
    )
    (net (code "83") (name "unconnected-(U2-GPIO11-Pad67)") (class "Default")
      (node (ref "U2") (pin "67") (pinfunction "GPIO11_67") (pintype "bidirectional"))
    )
    (net (code "84") (name "unconnected-(U2-GPIO12-Pad68)") (class "Default")
      (node (ref "U2") (pin "68") (pinfunction "GPIO12_68") (pintype "bidirectional"))
    )
    (net (code "85") (name "unconnected-(U2-LINEIN_L-Pad24)") (class "Default")
      (node (ref "U2") (pin "24") (pinfunction "LINEIN_L_24") (pintype "input"))
    )
    (net (code "86") (name "unconnected-(U2-LINEIN_R-Pad23)") (class "Default")
      (node (ref "U2") (pin "23") (pinfunction "LINEIN_R_23") (pintype "input"))
    )
    (net (code "87") (name "unconnected-(U2-MIC_N-Pad20)") (class "Default")
      (node (ref "U2") (pin "20") (pinfunction "MIC_N_20") (pintype "input"))
    )
    (net (code "88") (name "unconnected-(U2-MIC_P-Pad19)") (class "Default")
      (node (ref "U2") (pin "19") (pinfunction "MIC_P_19") (pintype "input"))
    )
    (net (code "89") (name "unconnected-(U2-NRESET-Pad16)") (class "Default")
      (node (ref "U2") (pin "16") (pinfunction "NRESET_16") (pintype "input"))
    )
    (net (code "90") (name "unconnected-(U2-PWM1-Pad35)") (class "Default")
      (node (ref "U2") (pin "35") (pinfunction "PWM1_35") (pintype "output"))
    )
    (net (code "91") (name "unconnected-(U2-PWM2-Pad36)") (class "Default")
      (node (ref "U2") (pin "36") (pinfunction "PWM2_36") (pintype "output"))
    )
    (net (code "92") (name "unconnected-(U2-PWRKEY_OUT-Pad2)") (class "Default")
      (node (ref "U2") (pin "2") (pinfunction "PWRKEY_OUT_2") (pintype "output"))
    )
    (net (code "93") (name "unconnected-(U2-RI-Pad4)") (class "Default")
      (node (ref "U2") (pin "4") (pinfunction "RI_4") (pintype "output"))
    )
    (net (code "94") (name "unconnected-(U2-RTS-Pad8)") (class "Default")
      (node (ref "U2") (pin "8") (pinfunction "RTS_8") (pintype "input"))
    )
    (net (code "95") (name "unconnected-(U2-SCL-Pad38)") (class "Default")
      (node (ref "U2") (pin "38") (pinfunction "SCL_38") (pintype "output"))
    )
    (net (code "96") (name "unconnected-(U2-SDA-Pad37)") (class "Default")
      (node (ref "U2") (pin "37") (pinfunction "SDA_37") (pintype "bidirectional"))
    )
    (net (code "97") (name "unconnected-(U2-SIM_PRESENCE-Pad34)") (class "Default")
      (node (ref "U2") (pin "34") (pinfunction "SIM_PRESENCE_34") (pintype "input"))
    )
    (net (code "98") (name "unconnected-(U2-SPK_N-Pad22)") (class "Default")
      (node (ref "U2") (pin "22") (pinfunction "SPK_N_22") (pintype "output"))
    )
    (net (code "99") (name "unconnected-(U2-SPK_P-Pad21)") (class "Default")
      (node (ref "U2") (pin "21") (pinfunction "SPK_P_21") (pintype "output"))
    )
    (net (code "100") (name "unconnected-(U2-VDD_EXT-Pad15)") (class "Default")
      (node (ref "U2") (pin "15") (pinfunction "VDD_EXT_15") (pintype "output"))
    )
    (net (code "101") (name "unconnected-(U3-ADC6-Pad19)") (class "Default")
      (node (ref "U3") (pin "19") (pinfunction "ADC6_19") (pintype "bidirectional"))
    )
    (net (code "102") (name "unconnected-(U3-ADC7-Pad22)") (class "Default")
      (node (ref "U3") (pin "22") (pinfunction "ADC7_22") (pintype "bidirectional"))
    )
    (net (code "103") (name "unconnected-(U3-PC3(ADC3)-Pad26)") (class "Default")
      (node (ref "U3") (pin "26") (pinfunction "PC3(ADC3)_26") (pintype "bidirectional"))
    )
    (net (code "104") (name "unconnected-(U3-PC4(ADC4{slash}SDA)-Pad27)") (class "Default")
      (node (ref "U3") (pin "27") (pinfunction "PC4(ADC4/SDA)_27") (pintype "bidirectional"))
    )
    (net (code "105") (name "unconnected-(U3-PC5(ADC5{slash}SCL)-Pad28)") (class "Default")
      (node (ref "U3") (pin "28") (pinfunction "PC5(ADC5/SCL)_28") (pintype "bidirectional"))
    )
  )
)
